# FAN_Dimmer_RE.net
KiCad netlist of a schematic drawn in EasyEDA
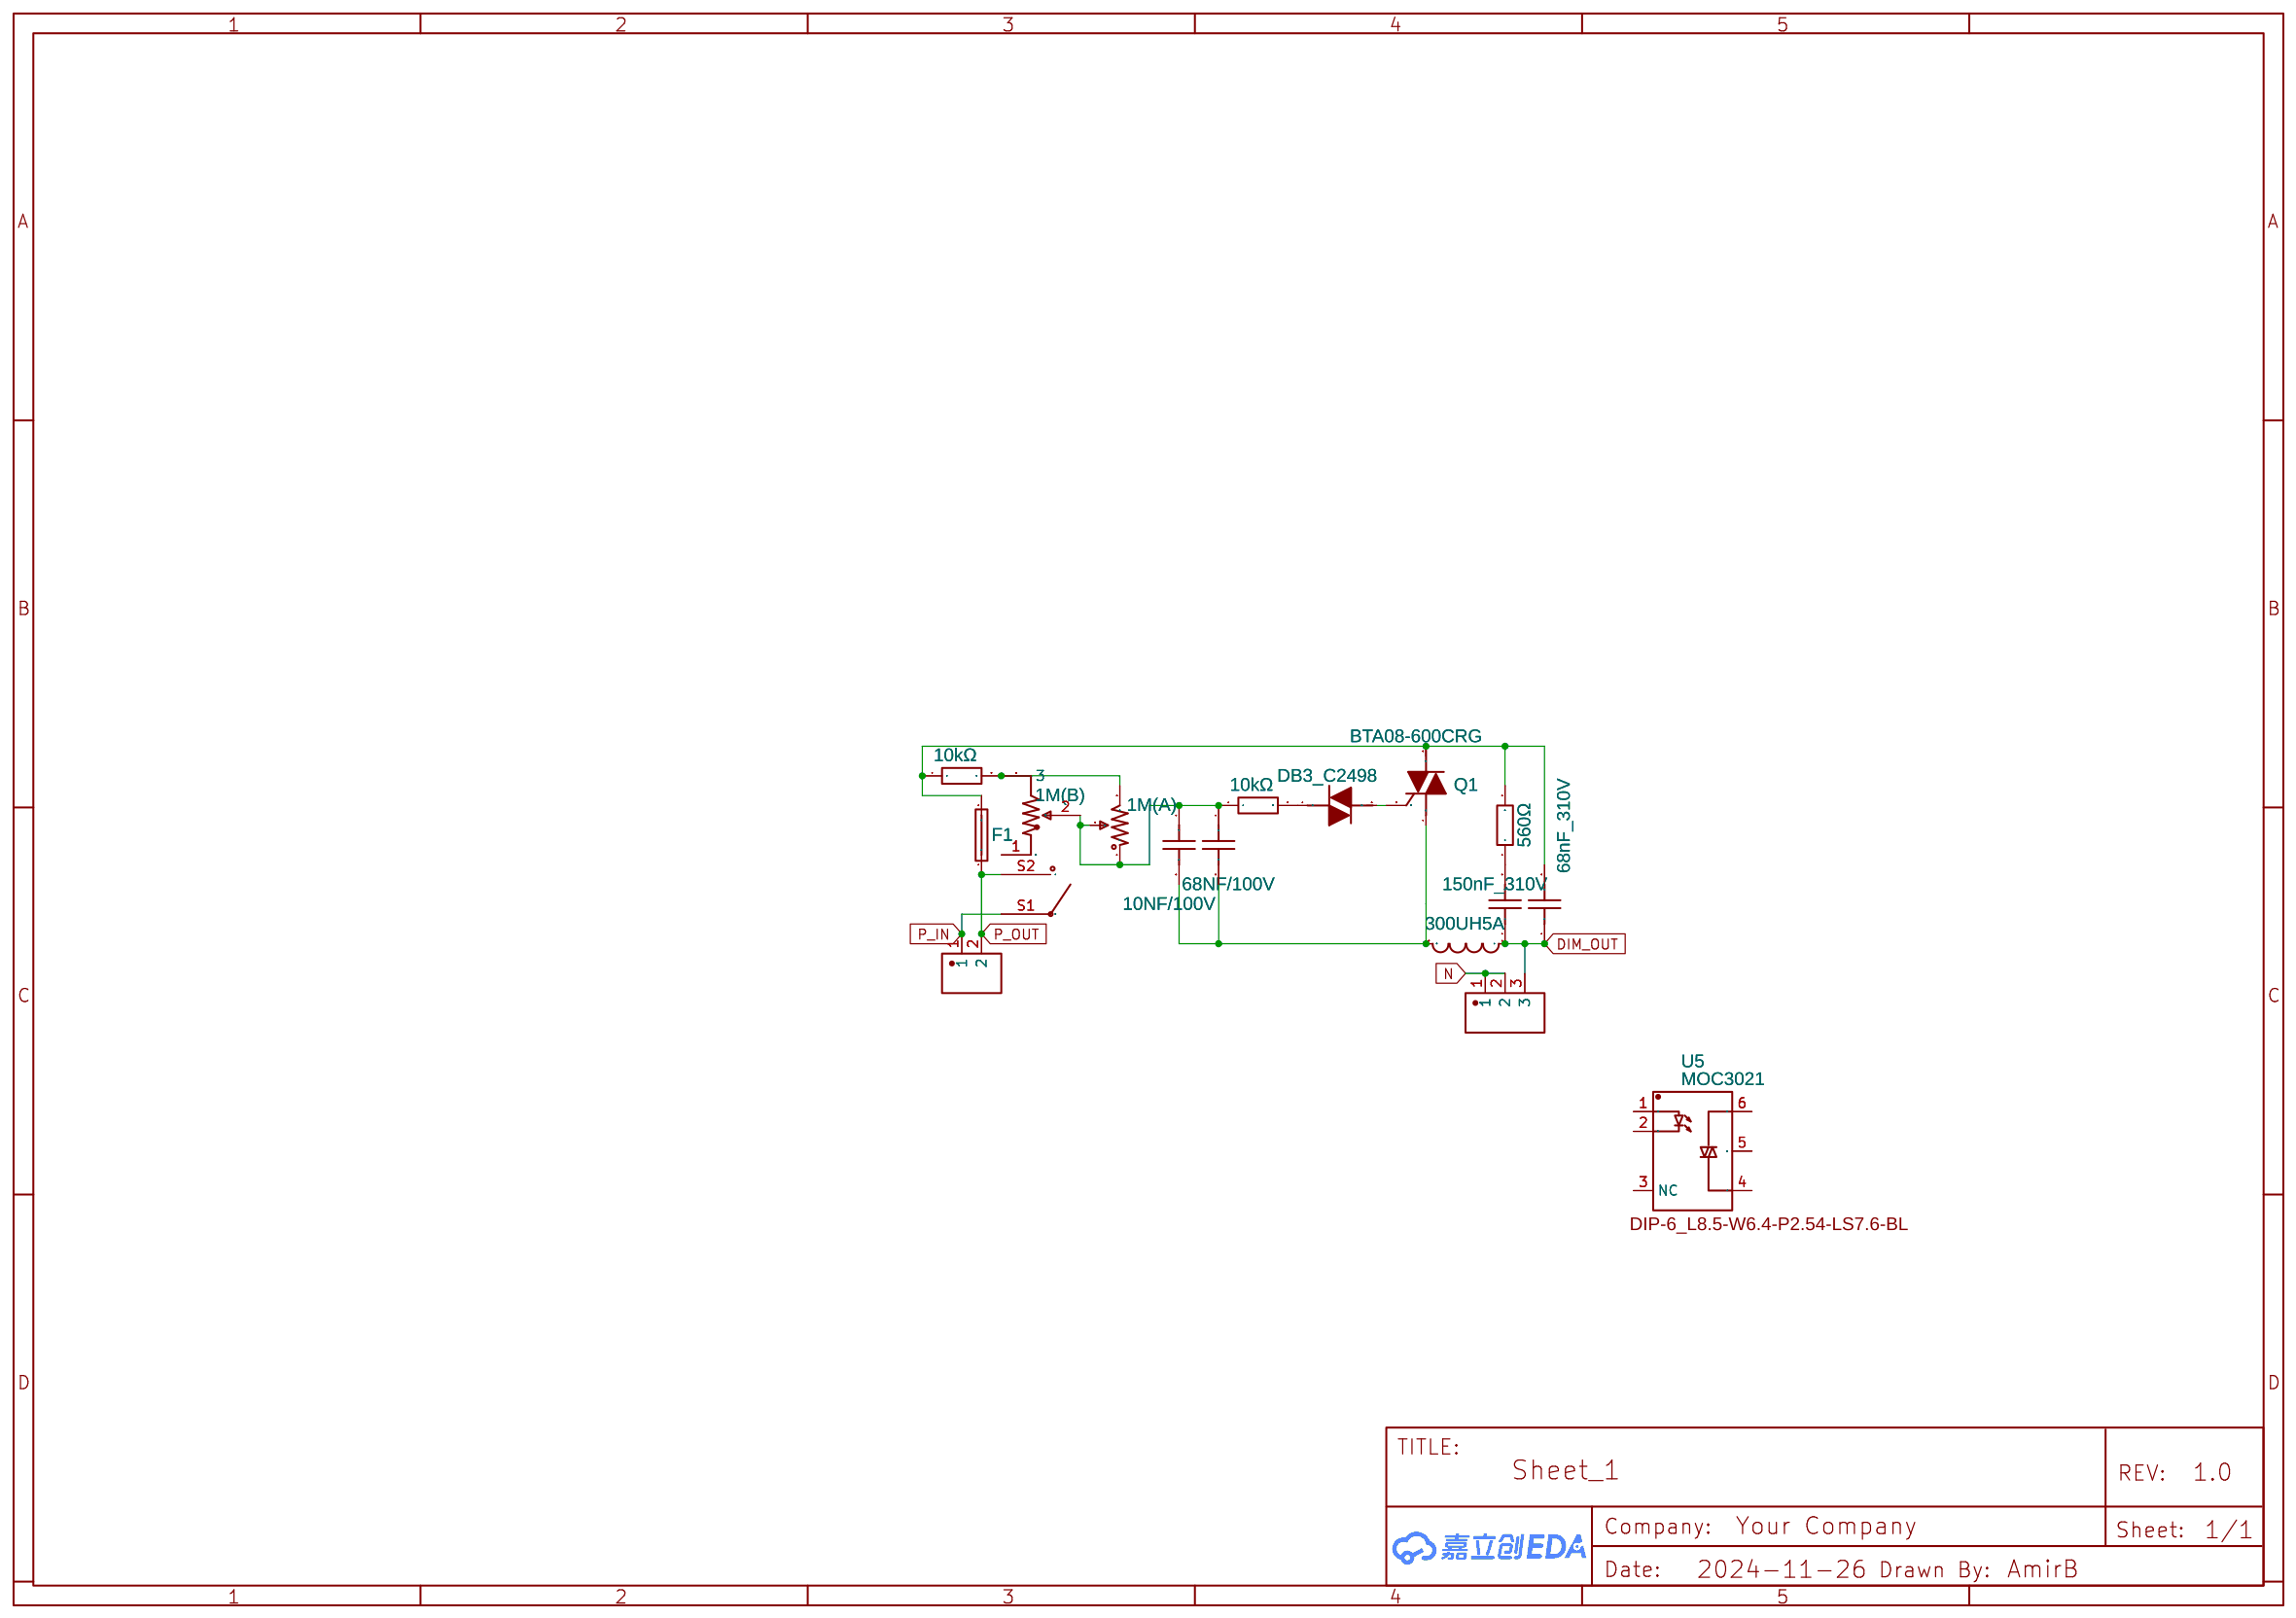
[diagram p0: schematic sheet]

(export (version "E")
  (design (tool "Eeschema 10.0.6"))
  (components
    (comp (ref "C1")
      (value "68NF/100V")
      (fields (field (name "Manufacturer Part") "68nF/1000V"))
      (libsource (lib "") (part "68NF/1000V"))
    )
    (comp (ref "C2")
      (value "10NF/100V")
      (fields (field (name "Manufacturer Part") "68nF/1000V"))
      (libsource (lib "") (part "68NF/1000V"))
    )
    (comp (ref "C3")
      (value "68nF_310V")
      (fields (field (name "Manufacturer Part") "K155K310VD7L15") (field (name "Manufacturer") "JIERONG(捷容)"))
      (libsource (lib "") (part "K155K310VD7L15"))
    )
    (comp (ref "C4")
      (value "150nF_310V")
      (fields (field (name "Manufacturer Part") "K155K310VD7L15") (field (name "Manufacturer") "JIERONG(捷容)"))
      (libsource (lib "") (part "K155K310VD7L15"))
    )
    (comp (ref "F1")
      (value "0215002.MXEP")
      (fields (field (name "Manufacturer") "Littelfuse(美国力特)"))
      (libsource (lib "") (part "0215002.MXEP"))
    )
    (comp (ref "P7")
      (value "1M(A)")
      (fields (field (name "Manufacturer Part") "3296W-1-103") (field (name "Manufacturer") "BOCHEN(博晨)"))
      (libsource (lib "") (part "3296W-1-103"))
    )
    (comp (ref "Q1")
      (value "BTA08-600CRG")
      (fields (field (name "Manufacturer") "ST(意法半导体)"))
      (libsource (lib "") (part "BTA08-600CRG"))
    )
    (comp (ref "Q3")
      (value "DB3_C2498")
      (fields (field (name "Manufacturer Part") "DB3") (field (name "Manufacturer") "ST(先科)"))
      (libsource (lib "") (part "DB3_C2498"))
    )
    (comp (ref "R2")
      (value "1M(B)")
      (fields (field (name "BOM_Manufacturer Part") "RV097NS") (field (name "BOM_Supplier Part") "undefined"))
      (libsource (lib "") (part "5Pin RV097NS with a Switch"))
    )
    (comp (ref "RL1V")
      (value "10kΩ")
      (fields
        (field (name "BOM_Manufacturer Part") "0603WAF1002T5E")
        (field (name "BOM_Supplier Part") "C25804")
      )
      (libsource (lib "") (part "0603WAF1002T5E_1"))
    )
    (comp (ref "RL12V")
      (value "10kΩ")
      (fields
        (field (name "BOM_Manufacturer Part") "0603WAF1002T5E")
        (field (name "BOM_Supplier Part") "C25804")
      )
      (libsource (lib "") (part "0603WAF1002T5E"))
    )
    (comp (ref "U1")
      (value "KF301R-5.0-3P")
      (fields (field (name "Manufacturer") "KEFA(科发)"))
      (libsource (lib "") (part "KF301R-5.0-3P"))
    )
    (comp (ref "U2")
      (value "KF301-5.0-2P")
      (fields (field (name "Manufacturer") "KEFA(科发)"))
      (libsource (lib "") (part "KF301-5.0-2P"))
    )
    (comp (ref "U3") (value "300UH5A") (libsource (lib "") (part "300UH5A")))
    (comp (ref "U4")
      (value "560Ω")
      (fields (field (name "Manufacturer Part") "CFR2WSJR-73-560R") (field (name "Manufacturer") "YAGEO(国巨)"))
      (libsource (lib "") (part "CFR2WSJR-73-560R"))
    )
    (comp (ref "U5")
      (value "MOC3021")
      (fields (field (name "Manufacturer") "LITEON(光宝)"))
      (libsource (lib "") (part "MOC3021"))
    )
  )
  (nets
    (net (code "1") (name "DIM_OUT") (class "Default")
      (node (ref "C3") (pin "1") (pinfunction "1_1") (pintype "unspecified"))
      (node (ref "C4") (pin "1") (pinfunction "1_1") (pintype "unspecified"))
      (node (ref "U1") (pin "3") (pinfunction "3_3") (pintype "unspecified"))
      (node (ref "U3") (pin "1") (pinfunction "1_1") (pintype "unspecified"))
    )
    (net (code "2") (name "N") (class "Default")
      (node (ref "U1") (pin "1") (pinfunction "1_1") (pintype "unspecified"))
      (node (ref "U1") (pin "2") (pinfunction "2_2") (pintype "unspecified"))
    )
    (net (code "3") (name "Net-(C4-Pad2)") (class "Default")
      (node (ref "C4") (pin "2") (pinfunction "2_2") (pintype "unspecified"))
      (node (ref "U4") (pin "1") (pinfunction "1_1") (pintype "unspecified"))
    )
    (net (code "4") (name "Net-(P7-Pad3)") (class "Default")
      (node (ref "P7") (pin "3") (pinfunction "3_3") (pintype "unspecified"))
      (node (ref "R2") (pin "3") (pinfunction "3_3") (pintype "unspecified"))
      (node (ref "RL1V") (pin "2") (pinfunction "2_2") (pintype "input"))
    )
    (net (code "5") (name "Net-(Q1-G)") (class "Default")
      (node (ref "Q1") (pin "3") (pinfunction "G_3") (pintype "unspecified"))
      (node (ref "Q3") (pin "2") (pinfunction "M2_2") (pintype "unspecified"))
    )
    (net (code "6") (name "Net-(Q1-M1)") (class "Default")
      (node (ref "C1") (pin "2") (pinfunction "2_2") (pintype "unspecified"))
      (node (ref "C2") (pin "2") (pinfunction "2_2") (pintype "unspecified"))
      (node (ref "Q1") (pin "1") (pinfunction "M1_1") (pintype "unspecified"))
      (node (ref "U3") (pin "2") (pinfunction "2_2") (pintype "unspecified"))
    )
    (net (code "7") (name "Net-(Q1-M2)") (class "Default")
      (node (ref "C3") (pin "2") (pinfunction "2_2") (pintype "unspecified"))
      (node (ref "F1") (pin "2") (pinfunction "2_2") (pintype "unspecified"))
      (node (ref "Q1") (pin "2") (pinfunction "M2_2") (pintype "unspecified"))
      (node (ref "RL1V") (pin "1") (pinfunction "1_1") (pintype "input"))
      (node (ref "U4") (pin "2") (pinfunction "2_2") (pintype "unspecified"))
    )
    (net (code "8") (name "Net-(Q3-M1)") (class "Default")
      (node (ref "Q3") (pin "1") (pinfunction "M1_1") (pintype "unspecified"))
      (node (ref "RL12V") (pin "2") (pinfunction "2_2") (pintype "input"))
    )
    (net (code "9") (name "Net-(R2-OUT)") (class "Default")
      (node (ref "C1") (pin "1") (pinfunction "1_1") (pintype "unspecified"))
      (node (ref "C2") (pin "1") (pinfunction "1_1") (pintype "unspecified"))
      (node (ref "P7") (pin "1") (pinfunction "1_1") (pintype "unspecified"))
      (node (ref "P7") (pin "2") (pinfunction "2_2") (pintype "unspecified"))
      (node (ref "R2") (pin "2") (pinfunction "OUT_2") (pintype "unspecified"))
      (node (ref "RL12V") (pin "1") (pinfunction "1_1") (pintype "input"))
    )
    (net (code "10") (name "P_IN") (class "Default")
      (node (ref "R2") (pin "S1") (pinfunction "2_S1") (pintype "unspecified"))
      (node (ref "U2") (pin "1") (pinfunction "1_1") (pintype "unspecified"))
    )
    (net (code "11") (name "P_OUT") (class "Default")
      (node (ref "F1") (pin "1") (pinfunction "1_1") (pintype "unspecified"))
      (node (ref "R2") (pin "S2") (pinfunction "1_S2") (pintype "unspecified"))
      (node (ref "U2") (pin "2") (pinfunction "2_2") (pintype "unspecified"))
    )
    (net (code "12") (name "unconnected-(R2-gnd-Pad1)") (class "Default")
      (node (ref "R2") (pin "1") (pinfunction "gnd_1") (pintype "unspecified"))
    )
    (net (code "13") (name "unconnected-(U5-BASE-Pad6)") (class "Default")
      (node (ref "U5") (pin "6") (pinfunction "BASE_6") (pintype "unspecified"))
    )
    (net (code "14") (name "unconnected-(U5-E-Pad4)") (class "Default")
      (node (ref "U5") (pin "4") (pinfunction "E_4") (pintype "unspecified"))
    )
    (net (code "15") (name "unconnected-(U5-NC-Pad3)") (class "Default")
      (node (ref "U5") (pin "3") (pinfunction "NC_3") (pintype "unspecified"))
    )
    (net (code "16") (name "unconnected-(U5-Pad1)") (class "Default")
      (node (ref "U5") (pin "1") (pinfunction "1_1") (pintype "unspecified"))
    )
    (net (code "17") (name "unconnected-(U5-Pad2)") (class "Default")
      (node (ref "U5") (pin "2") (pinfunction "2_2") (pintype "unspecified"))
    )
    (net (code "18") (name "unconnected-(U5-SUB-Pad5)") (class "Default")
      (node (ref "U5") (pin "5") (pinfunction "SUB_5") (pintype "unspecified"))
    )
  )
)
